# YOTSUBA__Y-Z_ver_1_0.net
KiCad netlist of a schematic drawn in EAGLE
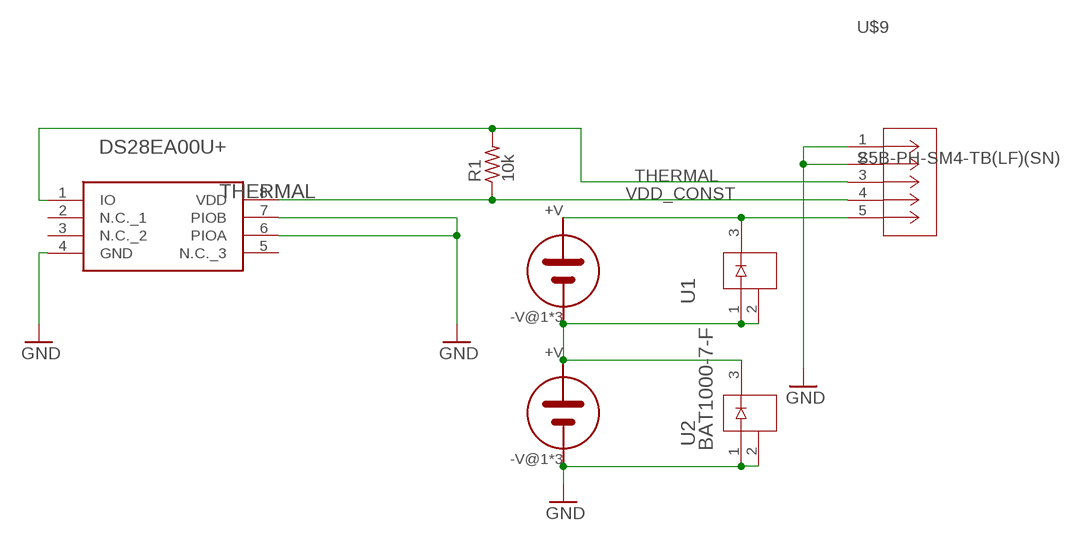
[diagram p0: schematic, sheet 1]

(export (version "E")
  (design (tool "Eeschema 10.0.6"))
  (components
    (comp (ref "R1")
      (value "10k")
      (footprint "eagle-import:R0805")
      (libsource (lib "eagle-import") (part "R-US_R0805"))
    )
    (comp (ref "THERMAL")
      (value "DS28EA00U+")
      (footprint "eagle-import:SOP65P490X110-8N")
      (fields (field (name "MOUSER_PART_NUMBER") "700-DS28EA00U"))
      (libsource (lib "eagle-import") (part "DS28EA00U+"))
    )
    (comp (ref "U$2")
      (value "3G30A")
      (footprint "eagle-import:SOLAR_3G30A")
      (libsource (lib "eagle-import") (part "3G30A"))
    )
    (comp (ref "U$3")
      (value "3G30A")
      (footprint "eagle-import:SOLAR_3G30A")
      (libsource (lib "eagle-import") (part "3G30A"))
    )
    (comp (ref "U$9")
      (value "S5B-PH-SM4-TB(LF)(SN)")
      (footprint "eagle-import:CONN_S5B-PH-SM4-TB_JST")
      (fields (field (name "COPYRIGHT") "Copyright (C) 2023 Ultra Librarian. All rights reserved."))
      (libsource (lib "eagle-import") (part "S5B-PH-SM4-TB(LF)(SN)"))
    )
    (comp (ref "U1")
      (value "BAT1000-7-F")
      (footprint "eagle-import:SOT23_BAT_DIO")
      (fields (field (name "COPYRIGHT") "Copyright (C) 2023 Ultra Librarian. All rights reserved."))
      (libsource (lib "eagle-import") (part "BAT1000-7-F"))
    )
    (comp (ref "U2")
      (value "BAT1000-7-F")
      (footprint "eagle-import:SOT23_BAT_DIO")
      (fields (field (name "COPYRIGHT") "Copyright (C) 2023 Ultra Librarian. All rights reserved."))
      (libsource (lib "eagle-import") (part "BAT1000-7-F"))
    )
  )
  (nets
    (net (code "1") (name "/THERMAL") (class "Default")
      (node (ref "R1") (pin "2") (pinfunction "2_2") (pintype "passive"))
      (node (ref "THERMAL") (pin "1") (pinfunction "IO_1") (pintype "bidirectional"))
      (node (ref "U$9") (pin "3") (pinfunction "3_3") (pintype "passive"))
    )
    (net (code "2") (name "/VDD_CONST") (class "Default")
      (node (ref "R1") (pin "1") (pinfunction "1_1") (pintype "passive"))
      (node (ref "THERMAL") (pin "8") (pinfunction "VDD_8") (pintype "bidirectional"))
      (node (ref "U$9") (pin "4") (pinfunction "4_4") (pintype "passive"))
    )
    (net (code "3") (name "GND") (class "Default")
      (node (ref "THERMAL") (pin "4") (pinfunction "GND_4") (pintype "bidirectional"))
      (node (ref "THERMAL") (pin "6") (pinfunction "PIOA_6") (pintype "bidirectional"))
      (node (ref "THERMAL") (pin "7") (pinfunction "PIOB_7") (pintype "bidirectional"))
      (node (ref "U$3") (pin "-V@1") (pinfunction "-V_-V@1") (pintype "bidirectional"))
      (node (ref "U$3") (pin "-V@2") (pinfunction "-V_-V@2") (pintype "bidirectional"))
      (node (ref "U$3") (pin "-V@3") (pinfunction "-V_-V@3") (pintype "bidirectional"))
      (node (ref "U$9") (pin "1") (pinfunction "1_1") (pintype "passive"))
      (node (ref "U$9") (pin "2") (pinfunction "2_2") (pintype "passive"))
      (node (ref "U2") (pin "1") (pinfunction "1_1") (pintype "passive"))
      (node (ref "U2") (pin "2") (pinfunction "2_2") (pintype "passive"))
    )
    (net (code "4") (name "Net-(U$2--V-Pad-V@1)") (class "Default")
      (node (ref "U$2") (pin "-V@1") (pinfunction "-V_-V@1") (pintype "bidirectional"))
      (node (ref "U$2") (pin "-V@2") (pinfunction "-V_-V@2") (pintype "bidirectional"))
      (node (ref "U$2") (pin "-V@3") (pinfunction "-V_-V@3") (pintype "bidirectional"))
      (node (ref "U$3") (pin "+V") (pinfunction "+V_+V") (pintype "bidirectional"))
      (node (ref "U1") (pin "1") (pinfunction "1_1") (pintype "passive"))
      (node (ref "U1") (pin "2") (pinfunction "2_2") (pintype "passive"))
      (node (ref "U2") (pin "3") (pinfunction "3_3") (pintype "passive"))
    )
    (net (code "5") (name "Net-(U$2-Pad+V)") (class "Default")
      (node (ref "U$2") (pin "+V") (pinfunction "+V_+V") (pintype "bidirectional"))
      (node (ref "U$9") (pin "5") (pinfunction "5_5") (pintype "passive"))
      (node (ref "U1") (pin "3") (pinfunction "3_3") (pintype "passive"))
    )
    (net (code "6") (name "unconnected-(THERMAL-N.C._1-Pad2)") (class "Default")
      (node (ref "THERMAL") (pin "2") (pinfunction "N.C._1_2") (pintype "bidirectional"))
    )
    (net (code "7") (name "unconnected-(THERMAL-N.C._2-Pad3)") (class "Default")
      (node (ref "THERMAL") (pin "3") (pinfunction "N.C._2_3") (pintype "bidirectional"))
    )
    (net (code "8") (name "unconnected-(THERMAL-N.C._3-Pad5)") (class "Default")
      (node (ref "THERMAL") (pin "5") (pinfunction "N.C._3_5") (pintype "bidirectional"))
    )
  )
)
